# display.net
KiCad netlist of a schematic drawn in Altium Designer
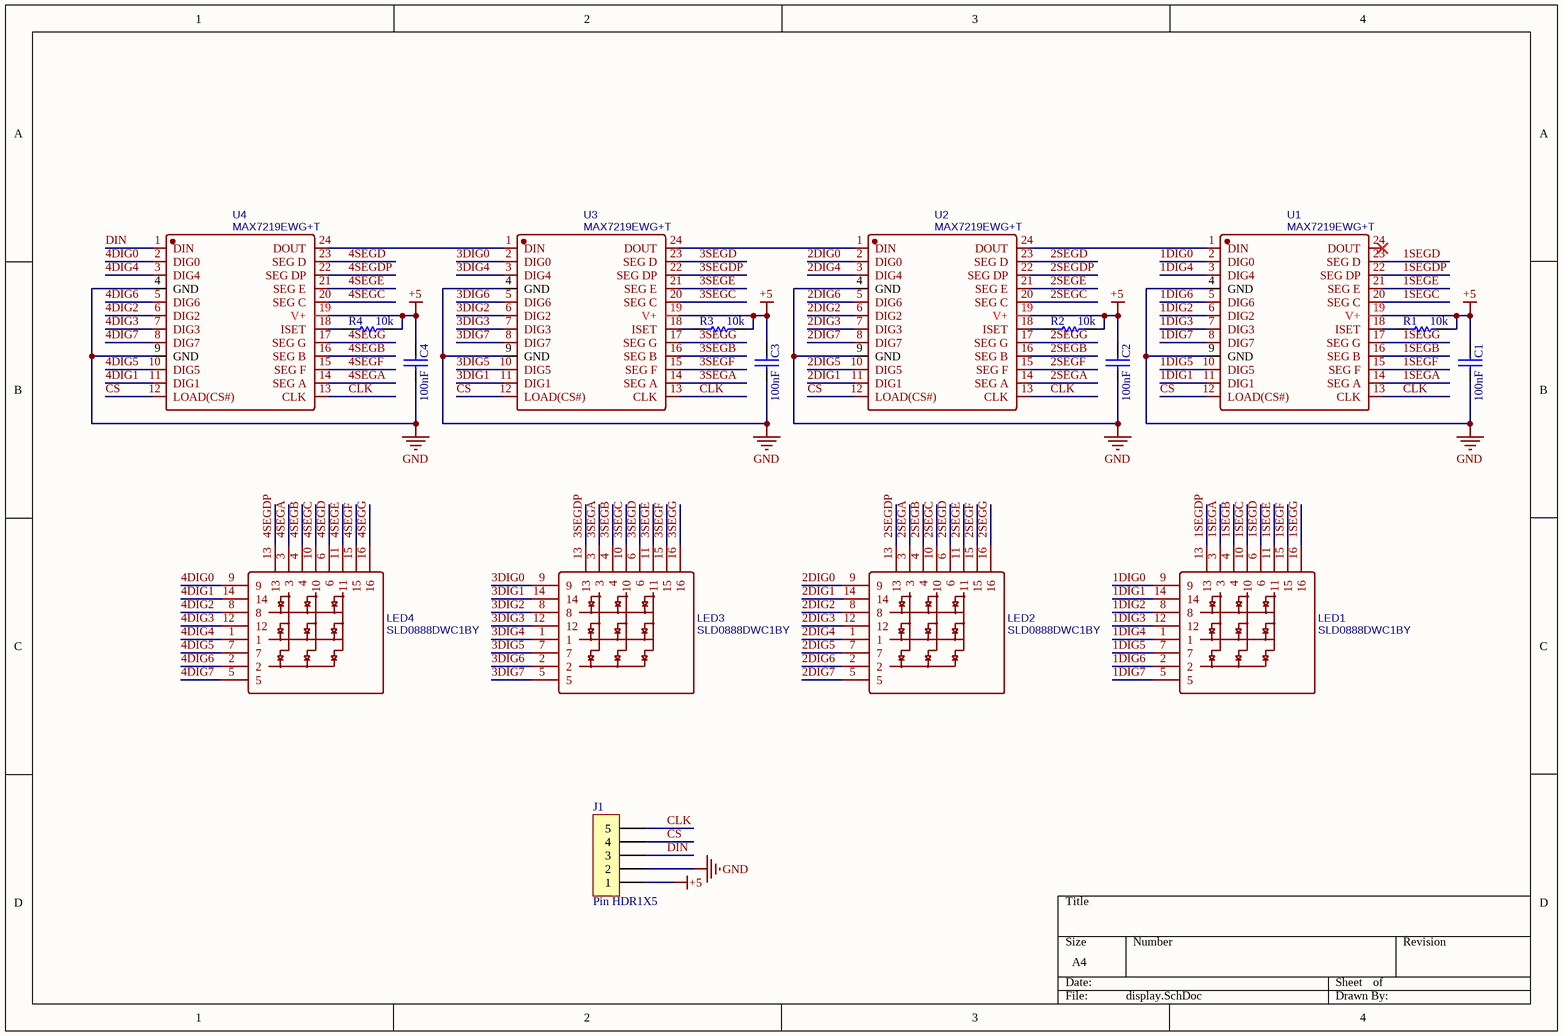
[diagram p0: display.SchDoc]

(export (version "E")
  (design (tool "Eeschema 10.0.6"))
  (components
    (comp (ref "C1")
      (value "100nF")
      (footprint "0201C")
      (description "无极性电容")
      (libsource (lib "电容") (part "CAP"))
    )
    (comp (ref "C2")
      (value "100nF")
      (footprint "0201C")
      (description "无极性电容")
      (libsource (lib "电容") (part "CAP"))
    )
    (comp (ref "C3")
      (value "100nF")
      (footprint "0201C")
      (description "无极性电容")
      (libsource (lib "电容") (part "CAP"))
    )
    (comp (ref "C4")
      (value "100nF")
      (footprint "0201C")
      (description "无极性电容")
      (libsource (lib "电容") (part "CAP"))
    )
    (comp (ref "J1")
      (value "Pin HDR1X5")
      (footprint "Pin HDR1X5/2mm-W")
      (libsource (lib "排针") (part "Pin HDR1X5"))
    )
    (comp (ref "LED1")
      (value "SLD0888DWC1BY")
      (footprint "点阵2cm")
      (fields (field (name "BOM_SUPPLIER PART") "C225986") (field (name "CONTRIBUTOR") "LCSC"))
      (libsource (lib "altium-import") (part "root_0_SLD0888DWC1BY_"))
    )
    (comp (ref "LED2")
      (value "SLD0888DWC1BY")
      (footprint "点阵2cm")
      (fields (field (name "BOM_SUPPLIER PART") "C225986") (field (name "CONTRIBUTOR") "LCSC"))
      (libsource (lib "altium-import") (part "root_0_SLD0888DWC1BY_"))
    )
    (comp (ref "LED3")
      (value "SLD0888DWC1BY")
      (footprint "点阵2cm")
      (fields (field (name "BOM_SUPPLIER PART") "C225986") (field (name "CONTRIBUTOR") "LCSC"))
      (libsource (lib "altium-import") (part "root_0_SLD0888DWC1BY_"))
    )
    (comp (ref "LED4")
      (value "SLD0888DWC1BY")
      (footprint "点阵2cm")
      (fields (field (name "BOM_SUPPLIER PART") "C225986") (field (name "CONTRIBUTOR") "LCSC"))
      (libsource (lib "altium-import") (part "root_0_SLD0888DWC1BY_"))
    )
    (comp (ref "R1") (value "10k") (footprint "0603R") (libsource (lib "电阻") (part "RES")))
    (comp (ref "R2") (value "10k") (footprint "0603R") (libsource (lib "电阻") (part "RES")))
    (comp (ref "R3") (value "10k") (footprint "0603R") (libsource (lib "电阻") (part "RES")))
    (comp (ref "R4") (value "10k") (footprint "0603R") (libsource (lib "电阻") (part "RES")))
    (comp (ref "U1")
      (value "MAX7219EWG+T")
      (footprint "MAX7219EWG")
      (fields (field (name "BOM_SUPPLIER PART") "C52476"))
      (libsource (lib "altium-import") (part "root_0_MAX7219EWG+T_"))
    )
    (comp (ref "U2")
      (value "MAX7219EWG+T")
      (footprint "MAX7219EWG")
      (fields (field (name "BOM_SUPPLIER PART") "C52476"))
      (libsource (lib "altium-import") (part "root_0_MAX7219EWG+T_"))
    )
    (comp (ref "U3")
      (value "MAX7219EWG+T")
      (footprint "MAX7219EWG")
      (fields (field (name "BOM_SUPPLIER PART") "C52476"))
      (libsource (lib "altium-import") (part "root_0_MAX7219EWG+T_"))
    )
    (comp (ref "U4")
      (value "MAX7219EWG+T")
      (footprint "MAX7219EWG")
      (fields (field (name "BOM_SUPPLIER PART") "C52476"))
      (libsource (lib "altium-import") (part "root_0_MAX7219EWG+T_"))
    )
  )
  (nets
    (net (code "1") (name "+5") (class "Default")
      (node (ref "C1") (pin "2") (pinfunction "2_2") (pintype "passive"))
      (node (ref "C2") (pin "2") (pinfunction "2_2") (pintype "passive"))
      (node (ref "C3") (pin "2") (pinfunction "2_2") (pintype "passive"))
      (node (ref "C4") (pin "2") (pinfunction "2_2") (pintype "passive"))
      (node (ref "J1") (pin "1") (pinfunction "1_1") (pintype "passive"))
      (node (ref "R1") (pin "2") (pinfunction "2_2") (pintype "passive"))
      (node (ref "R2") (pin "2") (pinfunction "2_2") (pintype "passive"))
      (node (ref "R3") (pin "2") (pinfunction "2_2") (pintype "passive"))
      (node (ref "R4") (pin "2") (pinfunction "2_2") (pintype "passive"))
      (node (ref "U1") (pin "19") (pinfunction "V+_19") (pintype "passive"))
      (node (ref "U2") (pin "19") (pinfunction "V+_19") (pintype "passive"))
      (node (ref "U3") (pin "19") (pinfunction "V+_19") (pintype "passive"))
      (node (ref "U4") (pin "19") (pinfunction "V+_19") (pintype "passive"))
    )
    (net (code "2") (name "/1DIG0") (class "Default")
      (node (ref "LED1") (pin "9") (pinfunction "9_9") (pintype "passive"))
      (node (ref "U1") (pin "2") (pinfunction "DIG0_2") (pintype "passive"))
    )
    (net (code "3") (name "/1DIG1") (class "Default")
      (node (ref "LED1") (pin "14") (pinfunction "14_14") (pintype "passive"))
      (node (ref "U1") (pin "11") (pinfunction "DIG1_11") (pintype "passive"))
    )
    (net (code "4") (name "/1DIG2") (class "Default")
      (node (ref "LED1") (pin "8") (pinfunction "8_8") (pintype "passive"))
      (node (ref "U1") (pin "6") (pinfunction "DIG2_6") (pintype "passive"))
    )
    (net (code "5") (name "/1DIG3") (class "Default")
      (node (ref "LED1") (pin "12") (pinfunction "12_12") (pintype "passive"))
      (node (ref "U1") (pin "7") (pinfunction "DIG3_7") (pintype "passive"))
    )
    (net (code "6") (name "/1DIG4") (class "Default")
      (node (ref "LED1") (pin "1") (pinfunction "1_1") (pintype "passive"))
      (node (ref "U1") (pin "3") (pinfunction "DIG4_3") (pintype "passive"))
    )
    (net (code "7") (name "/1DIG5") (class "Default")
      (node (ref "LED1") (pin "7") (pinfunction "7_7") (pintype "passive"))
      (node (ref "U1") (pin "10") (pinfunction "DIG5_10") (pintype "passive"))
    )
    (net (code "8") (name "/1DIG6") (class "Default")
      (node (ref "LED1") (pin "2") (pinfunction "2_2") (pintype "passive"))
      (node (ref "U1") (pin "5") (pinfunction "DIG6_5") (pintype "passive"))
    )
    (net (code "9") (name "/1DIG7") (class "Default")
      (node (ref "LED1") (pin "5") (pinfunction "5_5") (pintype "passive"))
      (node (ref "U1") (pin "8") (pinfunction "DIG7_8") (pintype "passive"))
    )
    (net (code "10") (name "/1SEGA") (class "Default")
      (node (ref "LED1") (pin "3") (pinfunction "3_3") (pintype "passive"))
      (node (ref "U1") (pin "14") (pinfunction "SEG_A_14") (pintype "passive"))
    )
    (net (code "11") (name "/1SEGB") (class "Default")
      (node (ref "LED1") (pin "4") (pinfunction "4_4") (pintype "passive"))
      (node (ref "U1") (pin "16") (pinfunction "SEG_B_16") (pintype "passive"))
    )
    (net (code "12") (name "/1SEGC") (class "Default")
      (node (ref "LED1") (pin "10") (pinfunction "10_10") (pintype "passive"))
      (node (ref "U1") (pin "20") (pinfunction "SEG_C_20") (pintype "passive"))
    )
    (net (code "13") (name "/1SEGD") (class "Default")
      (node (ref "LED1") (pin "6") (pinfunction "6_6") (pintype "passive"))
      (node (ref "U1") (pin "23") (pinfunction "SEG_D_23") (pintype "passive"))
    )
    (net (code "14") (name "/1SEGDP") (class "Default")
      (node (ref "LED1") (pin "13") (pinfunction "13_13") (pintype "passive"))
      (node (ref "U1") (pin "22") (pinfunction "SEG_DP_22") (pintype "passive"))
    )
    (net (code "15") (name "/1SEGE") (class "Default")
      (node (ref "LED1") (pin "11") (pinfunction "11_11") (pintype "passive"))
      (node (ref "U1") (pin "21") (pinfunction "SEG_E_21") (pintype "passive"))
    )
    (net (code "16") (name "/1SEGF") (class "Default")
      (node (ref "LED1") (pin "15") (pinfunction "15_15") (pintype "passive"))
      (node (ref "U1") (pin "15") (pinfunction "SEG_F_15") (pintype "passive"))
    )
    (net (code "17") (name "/1SEGG") (class "Default")
      (node (ref "LED1") (pin "16") (pinfunction "16_16") (pintype "passive"))
      (node (ref "U1") (pin "17") (pinfunction "SEG_G_17") (pintype "passive"))
    )
    (net (code "18") (name "/2DIG0") (class "Default")
      (node (ref "LED2") (pin "9") (pinfunction "9_9") (pintype "passive"))
      (node (ref "U2") (pin "2") (pinfunction "DIG0_2") (pintype "passive"))
    )
    (net (code "19") (name "/2DIG1") (class "Default")
      (node (ref "LED2") (pin "14") (pinfunction "14_14") (pintype "passive"))
      (node (ref "U2") (pin "11") (pinfunction "DIG1_11") (pintype "passive"))
    )
    (net (code "20") (name "/2DIG2") (class "Default")
      (node (ref "LED2") (pin "8") (pinfunction "8_8") (pintype "passive"))
      (node (ref "U2") (pin "6") (pinfunction "DIG2_6") (pintype "passive"))
    )
    (net (code "21") (name "/2DIG3") (class "Default")
      (node (ref "LED2") (pin "12") (pinfunction "12_12") (pintype "passive"))
      (node (ref "U2") (pin "7") (pinfunction "DIG3_7") (pintype "passive"))
    )
    (net (code "22") (name "/2DIG4") (class "Default")
      (node (ref "LED2") (pin "1") (pinfunction "1_1") (pintype "passive"))
      (node (ref "U2") (pin "3") (pinfunction "DIG4_3") (pintype "passive"))
    )
    (net (code "23") (name "/2DIG5") (class "Default")
      (node (ref "LED2") (pin "7") (pinfunction "7_7") (pintype "passive"))
      (node (ref "U2") (pin "10") (pinfunction "DIG5_10") (pintype "passive"))
    )
    (net (code "24") (name "/2DIG6") (class "Default")
      (node (ref "LED2") (pin "2") (pinfunction "2_2") (pintype "passive"))
      (node (ref "U2") (pin "5") (pinfunction "DIG6_5") (pintype "passive"))
    )
    (net (code "25") (name "/2DIG7") (class "Default")
      (node (ref "LED2") (pin "5") (pinfunction "5_5") (pintype "passive"))
      (node (ref "U2") (pin "8") (pinfunction "DIG7_8") (pintype "passive"))
    )
    (net (code "26") (name "/2SEGA") (class "Default")
      (node (ref "LED2") (pin "3") (pinfunction "3_3") (pintype "passive"))
      (node (ref "U2") (pin "14") (pinfunction "SEG_A_14") (pintype "passive"))
    )
    (net (code "27") (name "/2SEGB") (class "Default")
      (node (ref "LED2") (pin "4") (pinfunction "4_4") (pintype "passive"))
      (node (ref "U2") (pin "16") (pinfunction "SEG_B_16") (pintype "passive"))
    )
    (net (code "28") (name "/2SEGC") (class "Default")
      (node (ref "LED2") (pin "10") (pinfunction "10_10") (pintype "passive"))
      (node (ref "U2") (pin "20") (pinfunction "SEG_C_20") (pintype "passive"))
    )
    (net (code "29") (name "/2SEGD") (class "Default")
      (node (ref "LED2") (pin "6") (pinfunction "6_6") (pintype "passive"))
      (node (ref "U2") (pin "23") (pinfunction "SEG_D_23") (pintype "passive"))
    )
    (net (code "30") (name "/2SEGDP") (class "Default")
      (node (ref "LED2") (pin "13") (pinfunction "13_13") (pintype "passive"))
      (node (ref "U2") (pin "22") (pinfunction "SEG_DP_22") (pintype "passive"))
    )
    (net (code "31") (name "/2SEGE") (class "Default")
      (node (ref "LED2") (pin "11") (pinfunction "11_11") (pintype "passive"))
      (node (ref "U2") (pin "21") (pinfunction "SEG_E_21") (pintype "passive"))
    )
    (net (code "32") (name "/2SEGF") (class "Default")
      (node (ref "LED2") (pin "15") (pinfunction "15_15") (pintype "passive"))
      (node (ref "U2") (pin "15") (pinfunction "SEG_F_15") (pintype "passive"))
    )
    (net (code "33") (name "/2SEGG") (class "Default")
      (node (ref "LED2") (pin "16") (pinfunction "16_16") (pintype "passive"))
      (node (ref "U2") (pin "17") (pinfunction "SEG_G_17") (pintype "passive"))
    )
    (net (code "34") (name "/3DIG0") (class "Default")
      (node (ref "LED3") (pin "9") (pinfunction "9_9") (pintype "passive"))
      (node (ref "U3") (pin "2") (pinfunction "DIG0_2") (pintype "passive"))
    )
    (net (code "35") (name "/3DIG1") (class "Default")
      (node (ref "LED3") (pin "14") (pinfunction "14_14") (pintype "passive"))
      (node (ref "U3") (pin "11") (pinfunction "DIG1_11") (pintype "passive"))
    )
    (net (code "36") (name "/3DIG2") (class "Default")
      (node (ref "LED3") (pin "8") (pinfunction "8_8") (pintype "passive"))
      (node (ref "U3") (pin "6") (pinfunction "DIG2_6") (pintype "passive"))
    )
    (net (code "37") (name "/3DIG3") (class "Default")
      (node (ref "LED3") (pin "12") (pinfunction "12_12") (pintype "passive"))
      (node (ref "U3") (pin "7") (pinfunction "DIG3_7") (pintype "passive"))
    )
    (net (code "38") (name "/3DIG4") (class "Default")
      (node (ref "LED3") (pin "1") (pinfunction "1_1") (pintype "passive"))
      (node (ref "U3") (pin "3") (pinfunction "DIG4_3") (pintype "passive"))
    )
    (net (code "39") (name "/3DIG5") (class "Default")
      (node (ref "LED3") (pin "7") (pinfunction "7_7") (pintype "passive"))
      (node (ref "U3") (pin "10") (pinfunction "DIG5_10") (pintype "passive"))
    )
    (net (code "40") (name "/3DIG6") (class "Default")
      (node (ref "LED3") (pin "2") (pinfunction "2_2") (pintype "passive"))
      (node (ref "U3") (pin "5") (pinfunction "DIG6_5") (pintype "passive"))
    )
    (net (code "41") (name "/3DIG7") (class "Default")
      (node (ref "LED3") (pin "5") (pinfunction "5_5") (pintype "passive"))
      (node (ref "U3") (pin "8") (pinfunction "DIG7_8") (pintype "passive"))
    )
    (net (code "42") (name "/3SEGA") (class "Default")
      (node (ref "LED3") (pin "3") (pinfunction "3_3") (pintype "passive"))
      (node (ref "U3") (pin "14") (pinfunction "SEG_A_14") (pintype "passive"))
    )
    (net (code "43") (name "/3SEGB") (class "Default")
      (node (ref "LED3") (pin "4") (pinfunction "4_4") (pintype "passive"))
      (node (ref "U3") (pin "16") (pinfunction "SEG_B_16") (pintype "passive"))
    )
    (net (code "44") (name "/3SEGC") (class "Default")
      (node (ref "LED3") (pin "10") (pinfunction "10_10") (pintype "passive"))
      (node (ref "U3") (pin "20") (pinfunction "SEG_C_20") (pintype "passive"))
    )
    (net (code "45") (name "/3SEGD") (class "Default")
      (node (ref "LED3") (pin "6") (pinfunction "6_6") (pintype "passive"))
      (node (ref "U3") (pin "23") (pinfunction "SEG_D_23") (pintype "passive"))
    )
    (net (code "46") (name "/3SEGDP") (class "Default")
      (node (ref "LED3") (pin "13") (pinfunction "13_13") (pintype "passive"))
      (node (ref "U3") (pin "22") (pinfunction "SEG_DP_22") (pintype "passive"))
    )
    (net (code "47") (name "/3SEGE") (class "Default")
      (node (ref "LED3") (pin "11") (pinfunction "11_11") (pintype "passive"))
      (node (ref "U3") (pin "21") (pinfunction "SEG_E_21") (pintype "passive"))
    )
    (net (code "48") (name "/3SEGF") (class "Default")
      (node (ref "LED3") (pin "15") (pinfunction "15_15") (pintype "passive"))
      (node (ref "U3") (pin "15") (pinfunction "SEG_F_15") (pintype "passive"))
    )
    (net (code "49") (name "/3SEGG") (class "Default")
      (node (ref "LED3") (pin "16") (pinfunction "16_16") (pintype "passive"))
      (node (ref "U3") (pin "17") (pinfunction "SEG_G_17") (pintype "passive"))
    )
    (net (code "50") (name "/4DIG0") (class "Default")
      (node (ref "LED4") (pin "9") (pinfunction "9_9") (pintype "passive"))
      (node (ref "U4") (pin "2") (pinfunction "DIG0_2") (pintype "passive"))
    )
    (net (code "51") (name "/4DIG1") (class "Default")
      (node (ref "LED4") (pin "14") (pinfunction "14_14") (pintype "passive"))
      (node (ref "U4") (pin "11") (pinfunction "DIG1_11") (pintype "passive"))
    )
    (net (code "52") (name "/4DIG2") (class "Default")
      (node (ref "LED4") (pin "8") (pinfunction "8_8") (pintype "passive"))
      (node (ref "U4") (pin "6") (pinfunction "DIG2_6") (pintype "passive"))
    )
    (net (code "53") (name "/4DIG3") (class "Default")
      (node (ref "LED4") (pin "12") (pinfunction "12_12") (pintype "passive"))
      (node (ref "U4") (pin "7") (pinfunction "DIG3_7") (pintype "passive"))
    )
    (net (code "54") (name "/4DIG4") (class "Default")
      (node (ref "LED4") (pin "1") (pinfunction "1_1") (pintype "passive"))
      (node (ref "U4") (pin "3") (pinfunction "DIG4_3") (pintype "passive"))
    )
    (net (code "55") (name "/4DIG5") (class "Default")
      (node (ref "LED4") (pin "7") (pinfunction "7_7") (pintype "passive"))
      (node (ref "U4") (pin "10") (pinfunction "DIG5_10") (pintype "passive"))
    )
    (net (code "56") (name "/4DIG6") (class "Default")
      (node (ref "LED4") (pin "2") (pinfunction "2_2") (pintype "passive"))
      (node (ref "U4") (pin "5") (pinfunction "DIG6_5") (pintype "passive"))
    )
    (net (code "57") (name "/4DIG7") (class "Default")
      (node (ref "LED4") (pin "5") (pinfunction "5_5") (pintype "passive"))
      (node (ref "U4") (pin "8") (pinfunction "DIG7_8") (pintype "passive"))
    )
    (net (code "58") (name "/4SEGA") (class "Default")
      (node (ref "LED4") (pin "3") (pinfunction "3_3") (pintype "passive"))
      (node (ref "U4") (pin "14") (pinfunction "SEG_A_14") (pintype "passive"))
    )
    (net (code "59") (name "/4SEGB") (class "Default")
      (node (ref "LED4") (pin "4") (pinfunction "4_4") (pintype "passive"))
      (node (ref "U4") (pin "16") (pinfunction "SEG_B_16") (pintype "passive"))
    )
    (net (code "60") (name "/4SEGC") (class "Default")
      (node (ref "LED4") (pin "10") (pinfunction "10_10") (pintype "passive"))
      (node (ref "U4") (pin "20") (pinfunction "SEG_C_20") (pintype "passive"))
    )
    (net (code "61") (name "/4SEGD") (class "Default")
      (node (ref "LED4") (pin "6") (pinfunction "6_6") (pintype "passive"))
      (node (ref "U4") (pin "23") (pinfunction "SEG_D_23") (pintype "passive"))
    )
    (net (code "62") (name "/4SEGDP") (class "Default")
      (node (ref "LED4") (pin "13") (pinfunction "13_13") (pintype "passive"))
      (node (ref "U4") (pin "22") (pinfunction "SEG_DP_22") (pintype "passive"))
    )
    (net (code "63") (name "/4SEGE") (class "Default")
      (node (ref "LED4") (pin "11") (pinfunction "11_11") (pintype "passive"))
      (node (ref "U4") (pin "21") (pinfunction "SEG_E_21") (pintype "passive"))
    )
    (net (code "64") (name "/4SEGF") (class "Default")
      (node (ref "LED4") (pin "15") (pinfunction "15_15") (pintype "passive"))
      (node (ref "U4") (pin "15") (pinfunction "SEG_F_15") (pintype "passive"))
    )
    (net (code "65") (name "/4SEGG") (class "Default")
      (node (ref "LED4") (pin "16") (pinfunction "16_16") (pintype "passive"))
      (node (ref "U4") (pin "17") (pinfunction "SEG_G_17") (pintype "passive"))
    )
    (net (code "66") (name "/CLK") (class "Default")
      (node (ref "J1") (pin "5") (pinfunction "5_5") (pintype "passive"))
      (node (ref "U1") (pin "13") (pinfunction "CLK_13") (pintype "passive"))
      (node (ref "U2") (pin "13") (pinfunction "CLK_13") (pintype "passive"))
      (node (ref "U3") (pin "13") (pinfunction "CLK_13") (pintype "passive"))
      (node (ref "U4") (pin "13") (pinfunction "CLK_13") (pintype "passive"))
    )
    (net (code "67") (name "/CS") (class "Default")
      (node (ref "J1") (pin "4") (pinfunction "4_4") (pintype "passive"))
      (node (ref "U1") (pin "12") (pinfunction "LOAD(CS#)_12") (pintype "passive"))
      (node (ref "U2") (pin "12") (pinfunction "LOAD(CS#)_12") (pintype "passive"))
      (node (ref "U3") (pin "12") (pinfunction "LOAD(CS#)_12") (pintype "passive"))
      (node (ref "U4") (pin "12") (pinfunction "LOAD(CS#)_12") (pintype "passive"))
    )
    (net (code "68") (name "/DIN") (class "Default")
      (node (ref "J1") (pin "3") (pinfunction "3_3") (pintype "passive"))
      (node (ref "U4") (pin "1") (pinfunction "DIN_1") (pintype "passive"))
    )
    (net (code "69") (name "GND") (class "Default")
      (node (ref "C1") (pin "1") (pinfunction "1_1") (pintype "passive"))
      (node (ref "C2") (pin "1") (pinfunction "1_1") (pintype "passive"))
      (node (ref "C3") (pin "1") (pinfunction "1_1") (pintype "passive"))
      (node (ref "C4") (pin "1") (pinfunction "1_1") (pintype "passive"))
      (node (ref "J1") (pin "2") (pinfunction "2_2") (pintype "passive"))
      (node (ref "U1") (pin "4") (pinfunction "GND_4") (pintype "passive"))
      (node (ref "U1") (pin "9") (pinfunction "GND_9") (pintype "passive"))
      (node (ref "U2") (pin "4") (pinfunction "GND_4") (pintype "passive"))
      (node (ref "U2") (pin "9") (pinfunction "GND_9") (pintype "passive"))
      (node (ref "U3") (pin "4") (pinfunction "GND_4") (pintype "passive"))
      (node (ref "U3") (pin "9") (pinfunction "GND_9") (pintype "passive"))
      (node (ref "U4") (pin "4") (pinfunction "GND_4") (pintype "passive"))
      (node (ref "U4") (pin "9") (pinfunction "GND_9") (pintype "passive"))
    )
    (net (code "70") (name "Net-(U1-DIN)") (class "Default")
      (node (ref "U1") (pin "1") (pinfunction "DIN_1") (pintype "passive"))
      (node (ref "U2") (pin "24") (pinfunction "DOUT_24") (pintype "passive"))
    )
    (net (code "71") (name "Net-(U1-ISET)") (class "Default")
      (node (ref "R1") (pin "1") (pinfunction "1_1") (pintype "passive"))
      (node (ref "U1") (pin "18") (pinfunction "ISET_18") (pintype "passive"))
    )
    (net (code "72") (name "Net-(U2-DIN)") (class "Default")
      (node (ref "U2") (pin "1") (pinfunction "DIN_1") (pintype "passive"))
      (node (ref "U3") (pin "24") (pinfunction "DOUT_24") (pintype "passive"))
    )
    (net (code "73") (name "Net-(U2-ISET)") (class "Default")
      (node (ref "R2") (pin "1") (pinfunction "1_1") (pintype "passive"))
      (node (ref "U2") (pin "18") (pinfunction "ISET_18") (pintype "passive"))
    )
    (net (code "74") (name "Net-(U3-DIN)") (class "Default")
      (node (ref "U3") (pin "1") (pinfunction "DIN_1") (pintype "passive"))
      (node (ref "U4") (pin "24") (pinfunction "DOUT_24") (pintype "passive"))
    )
    (net (code "75") (name "Net-(U3-ISET)") (class "Default")
      (node (ref "R3") (pin "1") (pinfunction "1_1") (pintype "passive"))
      (node (ref "U3") (pin "18") (pinfunction "ISET_18") (pintype "passive"))
    )
    (net (code "76") (name "Net-(U4-ISET)") (class "Default")
      (node (ref "R4") (pin "1") (pinfunction "1_1") (pintype "passive"))
      (node (ref "U4") (pin "18") (pinfunction "ISET_18") (pintype "passive"))
    )
    (net (code "77") (name "unconnected-(U1-DOUT-Pad24)") (class "Default")
      (node (ref "U1") (pin "24") (pinfunction "DOUT_24") (pintype "passive+no_connect"))
    )
  )
)
